# Poprawiona.net
KiCad netlist of a schematic drawn in EAGLE
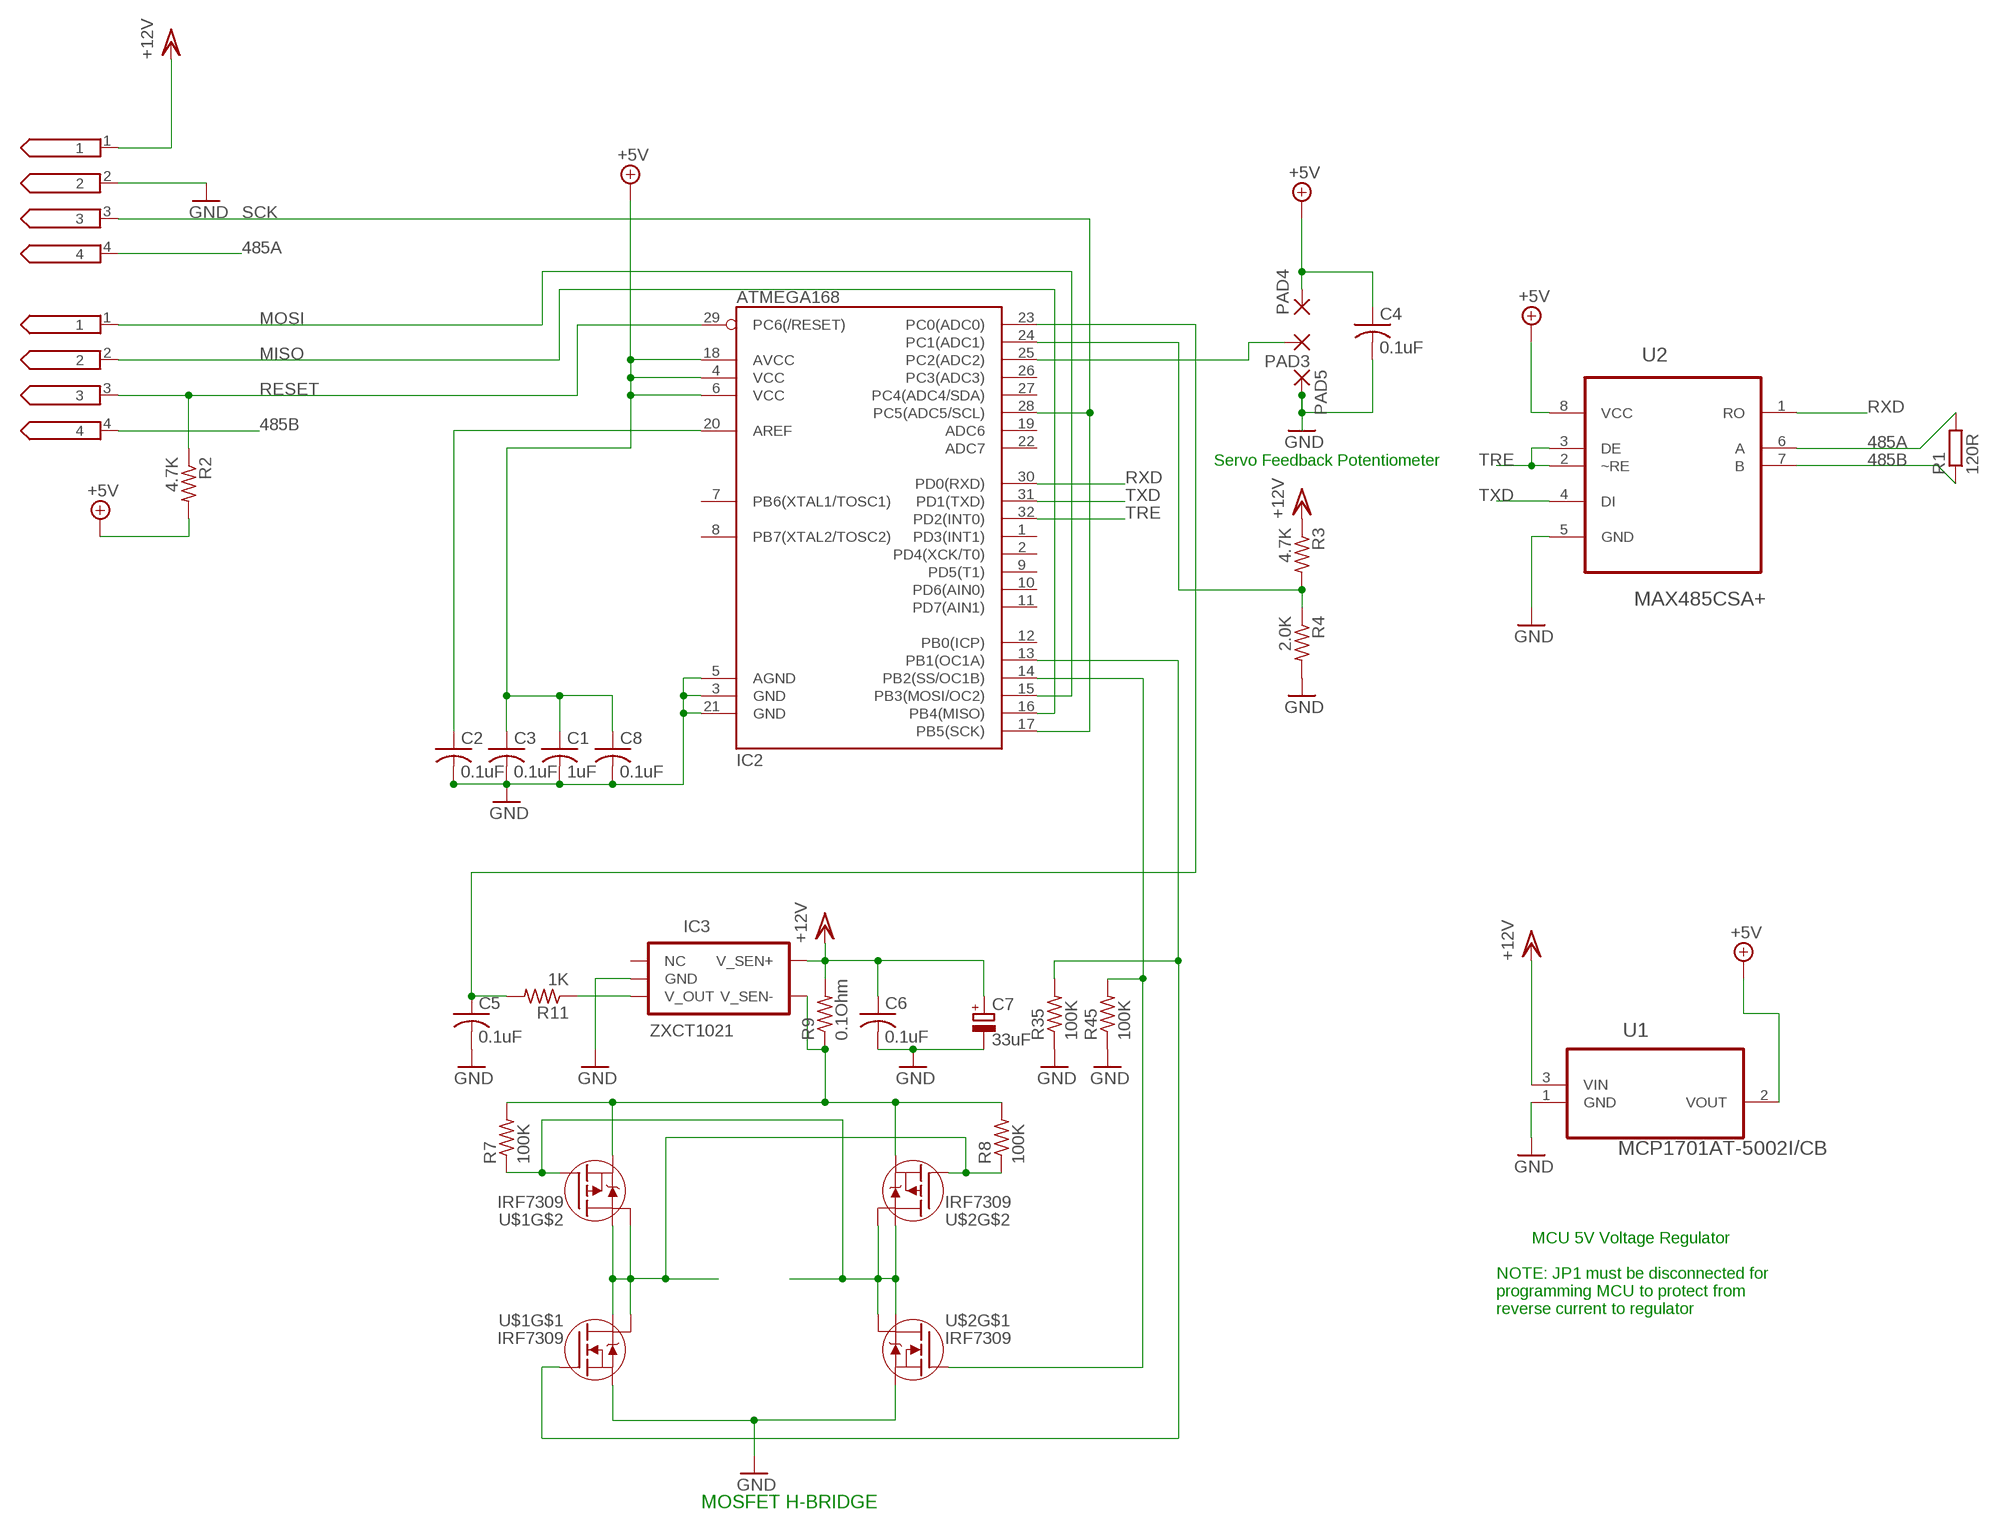
[diagram p0: schematic, sheet 1]

(export (version "E")
  (design (tool "Eeschema 10.0.6"))
  (components
    (comp (ref "C1")
      (value "1uF")
      (footprint "eagle-import:C0603")
      (libsource (lib "eagle-import") (part "C-USC0603"))
    )
    (comp (ref "C2")
      (value "0.1uF")
      (footprint "eagle-import:C0603")
      (libsource (lib "eagle-import") (part "C-USC0603"))
    )
    (comp (ref "C3")
      (value "0.1uF")
      (footprint "eagle-import:C0603")
      (libsource (lib "eagle-import") (part "C-USC0603"))
    )
    (comp (ref "C4")
      (value "0.1uF")
      (footprint "eagle-import:C0603")
      (libsource (lib "eagle-import") (part "C-USC0603"))
    )
    (comp (ref "C5")
      (value "0.1uF")
      (footprint "eagle-import:C0603K")
      (libsource (lib "eagle-import") (part "C-USC0603K"))
    )
    (comp (ref "C6")
      (value "0.1uF")
      (footprint "eagle-import:C0603")
      (libsource (lib "eagle-import") (part "C-USC0603"))
    )
    (comp (ref "C7")
      (value "33uF")
      (footprint "eagle-import:B_3528-21R")
      (libsource (lib "eagle-import") (part "CPOL-EUB/3528-21R"))
    )
    (comp (ref "C8")
      (value "0.1uF")
      (footprint "eagle-import:C0603")
      (libsource (lib "eagle-import") (part "C-USC0603"))
    )
    (comp (ref "IC2")
      (value "ATMEGA168")
      (footprint "eagle-import:TQFP32-08")
      (libsource (lib "eagle-import") (part "ATMEGA168"))
    )
    (comp (ref "IC3")
      (value "ZXCT1021")
      (footprint "eagle-import:SOT23-5")
      (libsource (lib "eagle-import") (part "ZXCT1021SOT23-5"))
    )
    (comp (ref "JP1")
      (value "4-EDGEVERSION2")
      (footprint "eagle-import:4-PIN-EDGE-V2")
      (libsource (lib "eagle-import") (part "4-EDGEVERSION2"))
    )
    (comp (ref "JP2")
      (value "4-EDGEVERSION2")
      (footprint "eagle-import:4-PIN-EDGE-V2")
      (libsource (lib "eagle-import") (part "4-EDGEVERSION2"))
    )
    (comp (ref "PAD3")
      (value "1,6/0,8")
      (footprint "eagle-import:1,6_0,8")
      (libsource (lib "eagle-import") (part "1,6/0,8"))
    )
    (comp (ref "PAD4")
      (value "1,6/0,8")
      (footprint "eagle-import:1,6_0,8")
      (libsource (lib "eagle-import") (part "1,6/0,8"))
    )
    (comp (ref "PAD5")
      (value "1,6/0,8")
      (footprint "eagle-import:1,6_0,8")
      (libsource (lib "eagle-import") (part "1,6/0,8"))
    )
    (comp (ref "R1")
      (value "120R")
      (footprint "eagle-import:R0603")
      (libsource (lib "eagle-import") (part "R-EU_R0603"))
    )
    (comp (ref "R2")
      (value "4.7K")
      (footprint "eagle-import:R0603")
      (libsource (lib "eagle-import") (part "R-US_R0603"))
    )
    (comp (ref "R3")
      (value "4.7K")
      (footprint "eagle-import:R0603")
      (libsource (lib "eagle-import") (part "R-US_R0603"))
    )
    (comp (ref "R4")
      (value "2.0K")
      (footprint "eagle-import:R0603")
      (libsource (lib "eagle-import") (part "R-US_R0603"))
    )
    (comp (ref "R7")
      (value "100K")
      (footprint "eagle-import:R0603")
      (libsource (lib "eagle-import") (part "R-US_R0603"))
    )
    (comp (ref "R8")
      (value "100K")
      (footprint "eagle-import:R0603")
      (libsource (lib "eagle-import") (part "R-US_R0603"))
    )
    (comp (ref "R9")
      (value "0.1Ohm")
      (footprint "eagle-import:R0603")
      (libsource (lib "eagle-import") (part "R-US_R0603"))
    )
    (comp (ref "R11")
      (value "1K")
      (footprint "eagle-import:R0603")
      (libsource (lib "eagle-import") (part "R-US_R0603"))
    )
    (comp (ref "R35")
      (value "100K")
      (footprint "eagle-import:R0603")
      (libsource (lib "eagle-import") (part "R-US_R0603"))
    )
    (comp (ref "R45")
      (value "100K")
      (footprint "eagle-import:R0603")
      (libsource (lib "eagle-import") (part "R-US_R0603"))
    )
    (comp (ref "U$1")
      (value "IRF7309")
      (footprint "eagle-import:SO8-2")
      (libsource (lib "eagle-import") (part "IRF7309"))
    )
    (comp (ref "U$2")
      (value "IRF7309")
      (footprint "eagle-import:SO8-2")
      (libsource (lib "eagle-import") (part "IRF7309"))
    )
    (comp (ref "U1")
      (value "MCP1701AT-5002I/CB")
      (footprint "eagle-import:SOT95P255X145-3N")
      (libsource (lib "eagle-import") (part "MCP1701AT-5002I/CB"))
    )
    (comp (ref "U2")
      (value "MAX485CSA+")
      (footprint "eagle-import:SOIC127P600X175-8N")
      (libsource (lib "eagle-import") (part "MAX485CSA+"))
    )
  )
  (nets
    (net (code "1") (name "+5V") (class "Default")
      (node (ref "C1") (pin "1") (pinfunction "1_1") (pintype "passive"))
      (node (ref "C3") (pin "1") (pinfunction "1_1") (pintype "passive"))
      (node (ref "C4") (pin "1") (pinfunction "1_1") (pintype "passive"))
      (node (ref "C8") (pin "1") (pinfunction "1_1") (pintype "passive"))
      (node (ref "IC2") (pin "18") (pinfunction "AVCC_18") (pintype "bidirectional"))
      (node (ref "IC2") (pin "4") (pinfunction "VCC_4") (pintype "bidirectional"))
      (node (ref "IC2") (pin "6") (pinfunction "VCC_6") (pintype "bidirectional"))
      (node (ref "PAD4") (pin "1") (pinfunction "P_1") (pintype "passive"))
      (node (ref "R2") (pin "2") (pinfunction "2_2") (pintype "passive"))
      (node (ref "U1") (pin "2") (pinfunction "VOUT_2") (pintype "output"))
      (node (ref "U2") (pin "8") (pinfunction "VCC_8") (pintype "power_in"))
    )
    (net (code "2") (name "+12V") (class "Default")
      (node (ref "C6") (pin "1") (pinfunction "1_1") (pintype "passive"))
      (node (ref "C7") (pin "+") (pinfunction "+_+") (pintype "passive"))
      (node (ref "IC3") (pin "4") (pinfunction "V_SEN+_4") (pintype "input"))
      (node (ref "JP1") (pin "1") (pinfunction "1_1") (pintype "bidirectional"))
      (node (ref "R3") (pin "1") (pinfunction "1_1") (pintype "passive"))
      (node (ref "R9") (pin "2") (pinfunction "2_2") (pintype "passive"))
      (node (ref "U1") (pin "3") (pinfunction "VIN_3") (pintype "input"))
    )
    (net (code "3") (name "/485A") (class "Default")
      (node (ref "JP1") (pin "4") (pinfunction "4_4") (pintype "bidirectional"))
      (node (ref "R1") (pin "2") (pinfunction "2_2") (pintype "passive"))
      (node (ref "U2") (pin "6") (pinfunction "A_6") (pintype "bidirectional"))
    )
    (net (code "4") (name "/485B") (class "Default")
      (node (ref "JP2") (pin "4") (pinfunction "4_4") (pintype "bidirectional"))
      (node (ref "R1") (pin "1") (pinfunction "1_1") (pintype "passive"))
      (node (ref "U2") (pin "7") (pinfunction "B_7") (pintype "bidirectional"))
    )
    (net (code "5") (name "/MISO") (class "Default")
      (node (ref "IC2") (pin "16") (pinfunction "PB4(MISO)_16") (pintype "bidirectional"))
      (node (ref "JP2") (pin "2") (pinfunction "2_2") (pintype "bidirectional"))
    )
    (net (code "6") (name "/MOSI") (class "Default")
      (node (ref "IC2") (pin "15") (pinfunction "PB3(MOSI/OC2)_15") (pintype "bidirectional"))
      (node (ref "JP2") (pin "1") (pinfunction "1_1") (pintype "bidirectional"))
    )
    (net (code "7") (name "/RESET") (class "Default")
      (node (ref "IC2") (pin "29") (pinfunction "PC6(/RESET)_29") (pintype "bidirectional"))
      (node (ref "JP2") (pin "3") (pinfunction "3_3") (pintype "bidirectional"))
      (node (ref "R2") (pin "1") (pinfunction "1_1") (pintype "passive"))
    )
    (net (code "8") (name "/RXD") (class "Default")
      (node (ref "IC2") (pin "30") (pinfunction "PD0(RXD)_30") (pintype "bidirectional"))
      (node (ref "U2") (pin "1") (pinfunction "RO_1") (pintype "output"))
    )
    (net (code "9") (name "/SCK") (class "Default")
      (node (ref "IC2") (pin "17") (pinfunction "PB5(SCK)_17") (pintype "bidirectional"))
      (node (ref "IC2") (pin "28") (pinfunction "PC5(ADC5/SCL)_28") (pintype "bidirectional"))
      (node (ref "JP1") (pin "3") (pinfunction "3_3") (pintype "bidirectional"))
    )
    (net (code "10") (name "/TRE") (class "Default")
      (node (ref "IC2") (pin "32") (pinfunction "PD2(INT0)_32") (pintype "bidirectional"))
      (node (ref "U2") (pin "2") (pinfunction "~{RE}_2") (pintype "input"))
      (node (ref "U2") (pin "3") (pinfunction "DE_3") (pintype "input"))
    )
    (net (code "11") (name "/TXD") (class "Default")
      (node (ref "IC2") (pin "31") (pinfunction "PD1(TXD)_31") (pintype "bidirectional"))
      (node (ref "U2") (pin "4") (pinfunction "DI_4") (pintype "input"))
    )
    (net (code "12") (name "GND") (class "Default")
      (node (ref "C1") (pin "2") (pinfunction "2_2") (pintype "passive"))
      (node (ref "C2") (pin "2") (pinfunction "2_2") (pintype "passive"))
      (node (ref "C3") (pin "2") (pinfunction "2_2") (pintype "passive"))
      (node (ref "C4") (pin "2") (pinfunction "2_2") (pintype "passive"))
      (node (ref "C5") (pin "2") (pinfunction "2_2") (pintype "passive"))
      (node (ref "C6") (pin "2") (pinfunction "2_2") (pintype "passive"))
      (node (ref "C7") (pin "-") (pinfunction "-_-") (pintype "passive"))
      (node (ref "C8") (pin "2") (pinfunction "2_2") (pintype "passive"))
      (node (ref "IC2") (pin "21") (pinfunction "GND_21") (pintype "bidirectional"))
      (node (ref "IC2") (pin "3") (pinfunction "GND_3") (pintype "bidirectional"))
      (node (ref "IC2") (pin "5") (pinfunction "AGND_5") (pintype "bidirectional"))
      (node (ref "IC3") (pin "2") (pinfunction "GND_2") (pintype "input"))
      (node (ref "JP1") (pin "2") (pinfunction "2_2") (pintype "bidirectional"))
      (node (ref "PAD5") (pin "1") (pinfunction "P_1") (pintype "passive"))
      (node (ref "R35") (pin "1") (pinfunction "1_1") (pintype "passive"))
      (node (ref "R4") (pin "2") (pinfunction "2_2") (pintype "passive"))
      (node (ref "R45") (pin "1") (pinfunction "1_1") (pintype "passive"))
      (node (ref "U$1") (pin "1") (pinfunction "S_1") (pintype "bidirectional"))
      (node (ref "U$2") (pin "1") (pinfunction "S_1") (pintype "bidirectional"))
      (node (ref "U1") (pin "1") (pinfunction "GND_1") (pintype "passive"))
      (node (ref "U2") (pin "5") (pinfunction "GND_5") (pintype "passive"))
    )
    (net (code "13") (name "Net-(IC2-AREF)") (class "Default")
      (node (ref "C2") (pin "1") (pinfunction "1_1") (pintype "passive"))
      (node (ref "IC2") (pin "20") (pinfunction "AREF_20") (pintype "bidirectional"))
    )
    (net (code "14") (name "Net-(IC2-PB1(OC1A))") (class "Default")
      (node (ref "IC2") (pin "13") (pinfunction "PB1(OC1A)_13") (pintype "bidirectional"))
      (node (ref "R35") (pin "2") (pinfunction "2_2") (pintype "passive"))
      (node (ref "U$1") (pin "2") (pinfunction "G_2") (pintype "bidirectional"))
    )
    (net (code "15") (name "Net-(IC2-PB2(SS{slash}OC1B))") (class "Default")
      (node (ref "IC2") (pin "14") (pinfunction "PB2(SS/OC1B)_14") (pintype "bidirectional"))
      (node (ref "R45") (pin "2") (pinfunction "2_2") (pintype "passive"))
      (node (ref "U$2") (pin "2") (pinfunction "G_2") (pintype "bidirectional"))
    )
    (net (code "16") (name "Net-(IC2-PC0(ADC0))") (class "Default")
      (node (ref "C5") (pin "1") (pinfunction "1_1") (pintype "passive"))
      (node (ref "IC2") (pin "23") (pinfunction "PC0(ADC0)_23") (pintype "bidirectional"))
      (node (ref "R11") (pin "2") (pinfunction "2_2") (pintype "passive"))
    )
    (net (code "17") (name "Net-(IC2-PC1(ADC1))") (class "Default")
      (node (ref "IC2") (pin "24") (pinfunction "PC1(ADC1)_24") (pintype "bidirectional"))
      (node (ref "R3") (pin "2") (pinfunction "2_2") (pintype "passive"))
      (node (ref "R4") (pin "1") (pinfunction "1_1") (pintype "passive"))
    )
    (net (code "18") (name "Net-(IC2-PC2(ADC2))") (class "Default")
      (node (ref "IC2") (pin "25") (pinfunction "PC2(ADC2)_25") (pintype "bidirectional"))
      (node (ref "PAD3") (pin "1") (pinfunction "P_1") (pintype "passive"))
    )
    (net (code "19") (name "Net-(IC3-V_OUT)") (class "Default")
      (node (ref "IC3") (pin "3") (pinfunction "V_OUT_3") (pintype "input"))
      (node (ref "R11") (pin "1") (pinfunction "1_1") (pintype "passive"))
    )
    (net (code "20") (name "Net-(IC3-V_SEN-)") (class "Default")
      (node (ref "IC3") (pin "5") (pinfunction "V_SEN-_5") (pintype "passive"))
      (node (ref "R7") (pin "2") (pinfunction "2_2") (pintype "passive"))
      (node (ref "R8") (pin "2") (pinfunction "2_2") (pintype "passive"))
      (node (ref "R9") (pin "1") (pinfunction "1_1") (pintype "passive"))
      (node (ref "U$1") (pin "3") (pinfunction "S_3") (pintype "bidirectional"))
      (node (ref "U$2") (pin "3") (pinfunction "S_3") (pintype "bidirectional"))
    )
    (net (code "21") (name "Net-(U$1B-G)") (class "Default")
      (node (ref "R7") (pin "1") (pinfunction "1_1") (pintype "passive"))
      (node (ref "U$1") (pin "4") (pinfunction "G_4") (pintype "bidirectional"))
      (node (ref "U$2") (pin "5") (pinfunction "D_5") (pintype "bidirectional"))
      (node (ref "U$2") (pin "6") (pinfunction "D_6") (pintype "bidirectional"))
      (node (ref "U$2") (pin "7") (pinfunction "D_7") (pintype "bidirectional"))
      (node (ref "U$2") (pin "8") (pinfunction "D_8") (pintype "bidirectional"))
    )
    (net (code "22") (name "Net-(U$2B-G)") (class "Default")
      (node (ref "R8") (pin "1") (pinfunction "1_1") (pintype "passive"))
      (node (ref "U$1") (pin "5") (pinfunction "D_5") (pintype "bidirectional"))
      (node (ref "U$1") (pin "6") (pinfunction "D_6") (pintype "bidirectional"))
      (node (ref "U$1") (pin "7") (pinfunction "D_7") (pintype "bidirectional"))
      (node (ref "U$1") (pin "8") (pinfunction "D_8") (pintype "bidirectional"))
      (node (ref "U$2") (pin "4") (pinfunction "G_4") (pintype "bidirectional"))
    )
    (net (code "23") (name "unconnected-(IC2-ADC6-Pad19)") (class "Default")
      (node (ref "IC2") (pin "19") (pinfunction "ADC6_19") (pintype "bidirectional"))
    )
    (net (code "24") (name "unconnected-(IC2-ADC7-Pad22)") (class "Default")
      (node (ref "IC2") (pin "22") (pinfunction "ADC7_22") (pintype "bidirectional"))
    )
    (net (code "25") (name "unconnected-(IC2-PB0(ICP)-Pad12)") (class "Default")
      (node (ref "IC2") (pin "12") (pinfunction "PB0(ICP)_12") (pintype "bidirectional"))
    )
    (net (code "26") (name "unconnected-(IC2-PB6(XTAL1{slash}TOSC1)-Pad7)") (class "Default")
      (node (ref "IC2") (pin "7") (pinfunction "PB6(XTAL1/TOSC1)_7") (pintype "bidirectional"))
    )
    (net (code "27") (name "unconnected-(IC2-PB7(XTAL2{slash}TOSC2)-Pad8)") (class "Default")
      (node (ref "IC2") (pin "8") (pinfunction "PB7(XTAL2/TOSC2)_8") (pintype "bidirectional"))
    )
    (net (code "28") (name "unconnected-(IC2-PC3(ADC3)-Pad26)") (class "Default")
      (node (ref "IC2") (pin "26") (pinfunction "PC3(ADC3)_26") (pintype "bidirectional"))
    )
    (net (code "29") (name "unconnected-(IC2-PC4(ADC4{slash}SDA)-Pad27)") (class "Default")
      (node (ref "IC2") (pin "27") (pinfunction "PC4(ADC4/SDA)_27") (pintype "bidirectional"))
    )
    (net (code "30") (name "unconnected-(IC2-PD3(INT1)-Pad1)") (class "Default")
      (node (ref "IC2") (pin "1") (pinfunction "PD3(INT1)_1") (pintype "bidirectional"))
    )
    (net (code "31") (name "unconnected-(IC2-PD4(XCK{slash}T0)-Pad2)") (class "Default")
      (node (ref "IC2") (pin "2") (pinfunction "PD4(XCK/T0)_2") (pintype "bidirectional"))
    )
    (net (code "32") (name "unconnected-(IC2-PD5(T1)-Pad9)") (class "Default")
      (node (ref "IC2") (pin "9") (pinfunction "PD5(T1)_9") (pintype "bidirectional"))
    )
    (net (code "33") (name "unconnected-(IC2-PD6(AIN0)-Pad10)") (class "Default")
      (node (ref "IC2") (pin "10") (pinfunction "PD6(AIN0)_10") (pintype "bidirectional"))
    )
    (net (code "34") (name "unconnected-(IC2-PD7(AIN1)-Pad11)") (class "Default")
      (node (ref "IC2") (pin "11") (pinfunction "PD7(AIN1)_11") (pintype "bidirectional"))
    )
    (net (code "35") (name "unconnected-(IC3-NC-Pad1)") (class "Default")
      (node (ref "IC3") (pin "1") (pinfunction "NC_1") (pintype "no_connect"))
    )
  )
)
